# DAQ_IO.net
KiCad netlist of a schematic drawn in Altium Designer
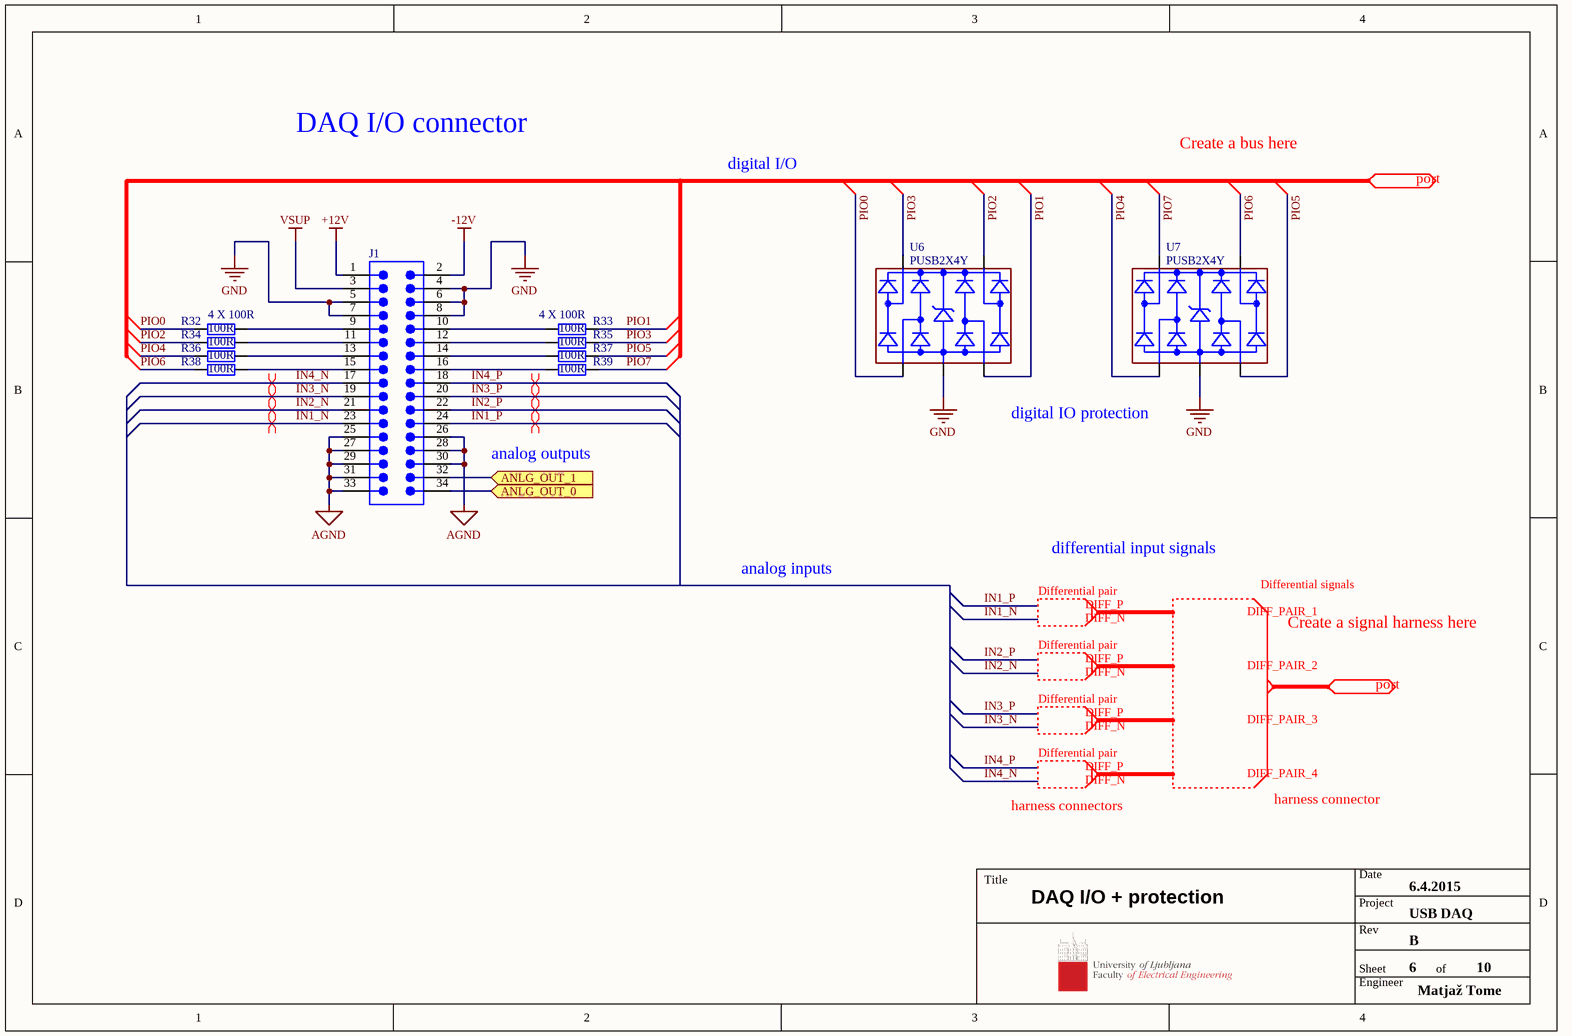
[diagram p0: DAQ_IO.SchDoc]

(export (version "E")
  (design (tool "Eeschema 10.0.6"))
  (components
    (comp (ref "J1")
      (value "2X17")
      (footprint "IDC34R")
      (description "Pin Header, Right Angle, Wire-to-Board, 2.54 mm, 2 Rows, 34 Contacts, Through Hole Right Angle")
      (fields (field (name "MANUFACTURER") "Harting"))
      (libsource (lib "DAQ") (part "09 18 534 7323"))
    )
    (comp (ref "R32")
      (value "100R")
      (footprint "R_0603")
      (description "Generic resistor")
      (fields (field (name "Comment") "comment"))
      (libsource (lib "DAQ") (part "Resistor"))
    )
    (comp (ref "R33")
      (value "100R")
      (footprint "R_0603")
      (description "Generic resistor")
      (fields (field (name "Comment") "comment"))
      (libsource (lib "DAQ") (part "Resistor"))
    )
    (comp (ref "R34")
      (value "100R")
      (footprint "R_0603")
      (description "Generic resistor")
      (fields (field (name "Comment") "comment"))
      (libsource (lib "DAQ") (part "Resistor"))
    )
    (comp (ref "R35")
      (value "100R")
      (footprint "R_0603")
      (description "Generic resistor")
      (fields (field (name "Comment") "comment"))
      (libsource (lib "DAQ") (part "Resistor"))
    )
    (comp (ref "R36")
      (value "100R")
      (footprint "R_0603")
      (description "Generic resistor")
      (fields (field (name "Comment") "comment"))
      (libsource (lib "DAQ") (part "Resistor"))
    )
    (comp (ref "R37")
      (value "100R")
      (footprint "R_0603")
      (description "Generic resistor")
      (fields (field (name "Comment") "comment"))
      (libsource (lib "DAQ") (part "Resistor"))
    )
    (comp (ref "R38")
      (value "100R")
      (footprint "R_0603")
      (description "Generic resistor")
      (fields (field (name "Comment") "comment"))
      (libsource (lib "DAQ") (part "Resistor"))
    )
    (comp (ref "R39")
      (value "100R")
      (footprint "R_0603")
      (description "Generic resistor")
      (fields (field (name "Comment") "comment"))
      (libsource (lib "DAQ") (part "Resistor"))
    )
    (comp (ref "U6")
      (value "PUSB2X4Y")
      (footprint "SOT363")
      (description "ESD protection for high-speed interfaces")
      (fields (field (name "PART NUMBER") "XDE0000") (field (name "MANUFACTURER") "Multicomp"))
      (libsource (lib "DAQ") (part "PUSB2X4Y"))
    )
    (comp (ref "U7")
      (value "PUSB2X4Y")
      (footprint "SOT363")
      (description "ESD protection for high-speed interfaces")
      (fields (field (name "PART NUMBER") "XDE0000") (field (name "MANUFACTURER") "Multicomp"))
      (libsource (lib "DAQ") (part "PUSB2X4Y"))
    )
  )
  (nets
    (net (code "1") (name "+12V") (class "Default")
      (node (ref "J1") (pin "1") (pinfunction "1_1") (pintype "passive"))
    )
    (net (code "2") (name "-12V") (class "Default")
      (node (ref "J1") (pin "2") (pinfunction "2_2") (pintype "passive"))
    )
    (net (code "3") (name "/ANLG_OUT_0") (class "Default")
      (node (ref "J1") (pin "34") (pinfunction "34_34") (pintype "passive"))
    )
    (net (code "4") (name "/ANLG_OUT_1") (class "Default")
      (node (ref "J1") (pin "32") (pinfunction "32_32") (pintype "passive"))
    )
    (net (code "5") (name "/IN1_N") (class "Default")
      (node (ref "J1") (pin "23") (pinfunction "23_23") (pintype "passive"))
    )
    (net (code "6") (name "/IN1_P") (class "Default")
      (node (ref "J1") (pin "24") (pinfunction "24_24") (pintype "passive"))
    )
    (net (code "7") (name "/IN2_N") (class "Default")
      (node (ref "J1") (pin "21") (pinfunction "21_21") (pintype "passive"))
    )
    (net (code "8") (name "/IN2_P") (class "Default")
      (node (ref "J1") (pin "22") (pinfunction "22_22") (pintype "passive"))
    )
    (net (code "9") (name "/IN3_N") (class "Default")
      (node (ref "J1") (pin "19") (pinfunction "19_19") (pintype "passive"))
    )
    (net (code "10") (name "/IN3_P") (class "Default")
      (node (ref "J1") (pin "20") (pinfunction "20_20") (pintype "passive"))
    )
    (net (code "11") (name "/IN4_N") (class "Default")
      (node (ref "J1") (pin "17") (pinfunction "17_17") (pintype "passive"))
    )
    (net (code "12") (name "/IN4_P") (class "Default")
      (node (ref "J1") (pin "18") (pinfunction "18_18") (pintype "passive"))
    )
    (net (code "13") (name "/PIO0") (class "Default")
      (node (ref "R32") (pin "1") (pintype "passive"))
      (node (ref "U6") (pin "1") (pinfunction "1_1") (pintype "passive"))
    )
    (net (code "14") (name "/PIO1") (class "Default")
      (node (ref "R33") (pin "2") (pintype "passive"))
      (node (ref "U6") (pin "3") (pinfunction "3_3") (pintype "passive"))
    )
    (net (code "15") (name "/PIO2") (class "Default")
      (node (ref "R34") (pin "1") (pintype "passive"))
      (node (ref "U6") (pin "4") (pinfunction "4_4") (pintype "passive"))
    )
    (net (code "16") (name "/PIO3") (class "Default")
      (node (ref "R35") (pin "2") (pintype "passive"))
      (node (ref "U6") (pin "6") (pinfunction "6_6") (pintype "passive"))
    )
    (net (code "17") (name "/PIO4") (class "Default")
      (node (ref "R36") (pin "1") (pintype "passive"))
      (node (ref "U7") (pin "1") (pinfunction "1_1") (pintype "passive"))
    )
    (net (code "18") (name "/PIO5") (class "Default")
      (node (ref "R37") (pin "2") (pintype "passive"))
      (node (ref "U7") (pin "3") (pinfunction "3_3") (pintype "passive"))
    )
    (net (code "19") (name "/PIO6") (class "Default")
      (node (ref "R38") (pin "1") (pintype "passive"))
      (node (ref "U7") (pin "4") (pinfunction "4_4") (pintype "passive"))
    )
    (net (code "20") (name "/PIO7") (class "Default")
      (node (ref "R39") (pin "2") (pintype "passive"))
      (node (ref "U7") (pin "6") (pinfunction "6_6") (pintype "passive"))
    )
    (net (code "21") (name "AGND") (class "Default")
      (node (ref "J1") (pin "25") (pinfunction "25_25") (pintype "passive"))
      (node (ref "J1") (pin "26") (pinfunction "26_26") (pintype "passive"))
      (node (ref "J1") (pin "27") (pinfunction "27_27") (pintype "passive"))
      (node (ref "J1") (pin "28") (pinfunction "28_28") (pintype "passive"))
      (node (ref "J1") (pin "29") (pinfunction "29_29") (pintype "passive"))
      (node (ref "J1") (pin "30") (pinfunction "30_30") (pintype "passive"))
      (node (ref "J1") (pin "31") (pinfunction "31_31") (pintype "passive"))
      (node (ref "J1") (pin "33") (pinfunction "33_33") (pintype "passive"))
    )
    (net (code "22") (name "GND") (class "Default")
      (node (ref "J1") (pin "4") (pinfunction "4_4") (pintype "passive"))
      (node (ref "J1") (pin "5") (pinfunction "5_5") (pintype "passive"))
      (node (ref "J1") (pin "6") (pinfunction "6_6") (pintype "passive"))
      (node (ref "J1") (pin "7") (pinfunction "7_7") (pintype "passive"))
      (node (ref "J1") (pin "8") (pinfunction "8_8") (pintype "passive"))
      (node (ref "U6") (pin "2") (pinfunction "2_2") (pintype "passive"))
      (node (ref "U7") (pin "2") (pinfunction "2_2") (pintype "passive"))
    )
    (net (code "23") (name "Net-(J1-Pad9)") (class "Default")
      (node (ref "J1") (pin "9") (pinfunction "9_9") (pintype "passive"))
      (node (ref "R32") (pin "2") (pintype "passive"))
    )
    (net (code "24") (name "Net-(J1-Pad10)") (class "Default")
      (node (ref "J1") (pin "10") (pinfunction "10_10") (pintype "passive"))
      (node (ref "R33") (pin "1") (pintype "passive"))
    )
    (net (code "25") (name "Net-(J1-Pad11)") (class "Default")
      (node (ref "J1") (pin "11") (pinfunction "11_11") (pintype "passive"))
      (node (ref "R34") (pin "2") (pintype "passive"))
    )
    (net (code "26") (name "Net-(J1-Pad12)") (class "Default")
      (node (ref "J1") (pin "12") (pinfunction "12_12") (pintype "passive"))
      (node (ref "R35") (pin "1") (pintype "passive"))
    )
    (net (code "27") (name "Net-(J1-Pad13)") (class "Default")
      (node (ref "J1") (pin "13") (pinfunction "13_13") (pintype "passive"))
      (node (ref "R36") (pin "2") (pintype "passive"))
    )
    (net (code "28") (name "Net-(J1-Pad14)") (class "Default")
      (node (ref "J1") (pin "14") (pinfunction "14_14") (pintype "passive"))
      (node (ref "R37") (pin "1") (pintype "passive"))
    )
    (net (code "29") (name "Net-(J1-Pad15)") (class "Default")
      (node (ref "J1") (pin "15") (pinfunction "15_15") (pintype "passive"))
      (node (ref "R38") (pin "2") (pintype "passive"))
    )
    (net (code "30") (name "Net-(J1-Pad16)") (class "Default")
      (node (ref "J1") (pin "16") (pinfunction "16_16") (pintype "passive"))
      (node (ref "R39") (pin "1") (pintype "passive"))
    )
    (net (code "31") (name "VSUP") (class "Default")
      (node (ref "J1") (pin "3") (pinfunction "3_3") (pintype "passive"))
    )
  )
)
